# Motor_Lab_v8.net
KiCad netlist of a schematic drawn in EAGLE
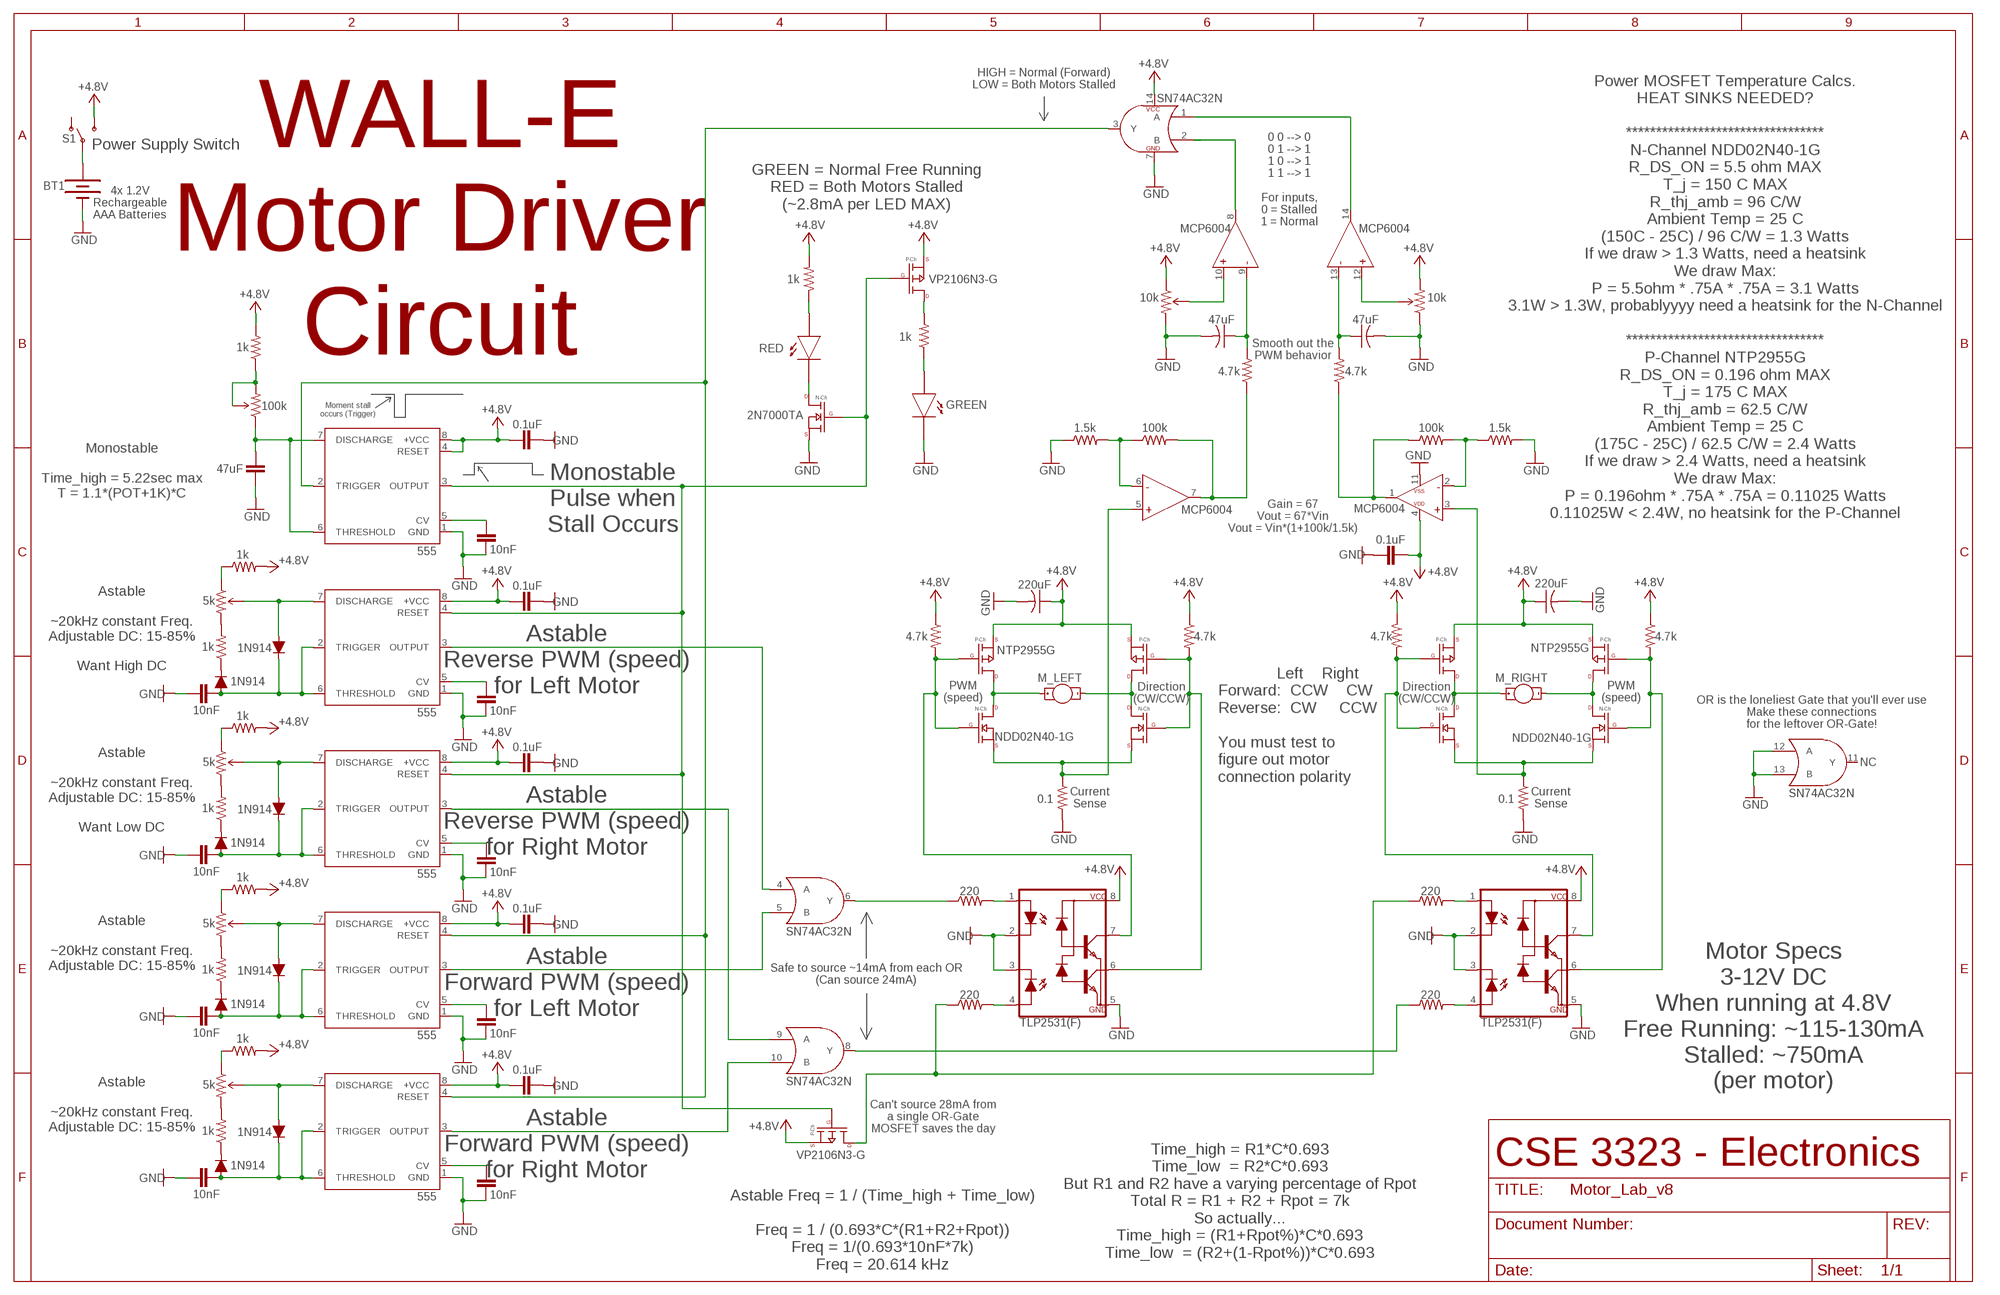
[diagram p0: schematic, sheet 1]

(export (version "E")
  (design (tool "Eeschema 10.0.6"))
  (components
    (comp (ref "BT1")
      (value "BATTERY-AAA")
      (footprint "eagle-import:BATTERY-AAA")
      (libsource (lib "eagle-import") (part "BATTERY-AAA"))
    )
    (comp (ref "C1")
      (value "220uF")
      (footprint "eagle-import:C025-024X044")
      (libsource (lib "eagle-import") (part "C-US025-024X044"))
    )
    (comp (ref "C2")
      (value "220uF")
      (footprint "eagle-import:C025-024X044")
      (libsource (lib "eagle-import") (part "C-US025-024X044"))
    )
    (comp (ref "C3")
      (value "0.1uF")
      (footprint "eagle-import:CAP-PTH-SMALL-KIT")
      (libsource (lib "eagle-import") (part "0.1UF-KIT-EZ-50V-20%"))
    )
    (comp (ref "C5")
      (value "0.1uF")
      (footprint "eagle-import:CAP-PTH-SMALL-KIT")
      (libsource (lib "eagle-import") (part "0.1UF-KIT-EZ-50V-20%"))
    )
    (comp (ref "C6")
      (value "10nF")
      (footprint "eagle-import:CAP-PTH-SMALL-KIT")
      (libsource (lib "eagle-import") (part "0.1UF-KIT-EZ-50V-20%"))
    )
    (comp (ref "C7")
      (value "10nF")
      (footprint "eagle-import:CAP-PTH-SMALL-KIT")
      (libsource (lib "eagle-import") (part "0.1UF-KIT-EZ-50V-20%"))
    )
    (comp (ref "C8")
      (value "0.1uF")
      (footprint "eagle-import:CAP-PTH-SMALL-KIT")
      (libsource (lib "eagle-import") (part "0.1UF-KIT-EZ-50V-20%"))
    )
    (comp (ref "C9")
      (value "10nF")
      (footprint "eagle-import:CAP-PTH-SMALL-KIT")
      (libsource (lib "eagle-import") (part "0.1UF-KIT-EZ-50V-20%"))
    )
    (comp (ref "C10")
      (value "0.1uF")
      (footprint "eagle-import:CAP-PTH-SMALL-KIT")
      (libsource (lib "eagle-import") (part "0.1UF-KIT-EZ-50V-20%"))
    )
    (comp (ref "C11")
      (value "10nF")
      (footprint "eagle-import:CAP-PTH-SMALL-KIT")
      (libsource (lib "eagle-import") (part "0.1UF-KIT-EZ-50V-20%"))
    )
    (comp (ref "C12")
      (value "0.1uF")
      (footprint "eagle-import:CAP-PTH-SMALL-KIT")
      (libsource (lib "eagle-import") (part "0.1UF-KIT-EZ-50V-20%"))
    )
    (comp (ref "C13")
      (value "10nF")
      (footprint "eagle-import:CAP-PTH-SMALL-KIT")
      (libsource (lib "eagle-import") (part "0.1UF-KIT-EZ-50V-20%"))
    )
    (comp (ref "C14")
      (value "0.1uF")
      (footprint "eagle-import:CAP-PTH-SMALL-KIT")
      (libsource (lib "eagle-import") (part "0.1UF-KIT-EZ-50V-20%"))
    )
    (comp (ref "C15")
      (value "10nF")
      (footprint "eagle-import:CAP-PTH-SMALL-KIT")
      (libsource (lib "eagle-import") (part "0.1UF-KIT-EZ-50V-20%"))
    )
    (comp (ref "C16")
      (value "10nF")
      (footprint "eagle-import:CAP-PTH-SMALL-KIT")
      (libsource (lib "eagle-import") (part "0.1UF-KIT-EZ-50V-20%"))
    )
    (comp (ref "C17")
      (value "10nF")
      (footprint "eagle-import:CAP-PTH-SMALL-KIT")
      (libsource (lib "eagle-import") (part "0.1UF-KIT-EZ-50V-20%"))
    )
    (comp (ref "C18")
      (value "10nF")
      (footprint "eagle-import:CAP-PTH-SMALL-KIT")
      (libsource (lib "eagle-import") (part "0.1UF-KIT-EZ-50V-20%"))
    )
    (comp (ref "C19")
      (value "47uF")
      (footprint "eagle-import:CAP-PTH-SMALL-KIT")
      (libsource (lib "eagle-import") (part "0.1UF-KIT-EZ-50V-20%"))
    )
    (comp (ref "C20")
      (value "47uF")
      (footprint "eagle-import:C025-024X044")
      (libsource (lib "eagle-import") (part "C-US025-024X044"))
    )
    (comp (ref "C22")
      (value "47uF")
      (footprint "eagle-import:C025-024X044")
      (libsource (lib "eagle-import") (part "C-US025-024X044"))
    )
    (comp (ref "D1")
      (value "RED")
      (footprint "eagle-import:LED5MM")
      (libsource (lib "eagle-import") (part "LED_5MM"))
    )
    (comp (ref "D2")
      (value "GREEN")
      (footprint "eagle-import:LED5MM")
      (libsource (lib "eagle-import") (part "LED_5MM"))
    )
    (comp (ref "D3")
      (value "1N914")
      (footprint "eagle-import:DIODE-1N4148")
      (libsource (lib "eagle-import") (part "DIODE-1N4148"))
    )
    (comp (ref "D4")
      (value "1N914")
      (footprint "eagle-import:DIODE-1N4148")
      (libsource (lib "eagle-import") (part "DIODE-1N4148"))
    )
    (comp (ref "D5")
      (value "1N914")
      (footprint "eagle-import:DIODE-1N4148")
      (libsource (lib "eagle-import") (part "DIODE-1N4148"))
    )
    (comp (ref "D6")
      (value "1N914")
      (footprint "eagle-import:DIODE-1N4148")
      (libsource (lib "eagle-import") (part "DIODE-1N4148"))
    )
    (comp (ref "D7")
      (value "1N914")
      (footprint "eagle-import:DIODE-1N4148")
      (libsource (lib "eagle-import") (part "DIODE-1N4148"))
    )
    (comp (ref "D8")
      (value "1N914")
      (footprint "eagle-import:DIODE-1N4148")
      (libsource (lib "eagle-import") (part "DIODE-1N4148"))
    )
    (comp (ref "D9")
      (value "1N914")
      (footprint "eagle-import:DIODE-1N4148")
      (libsource (lib "eagle-import") (part "DIODE-1N4148"))
    )
    (comp (ref "D10")
      (value "1N914")
      (footprint "eagle-import:DIODE-1N4148")
      (libsource (lib "eagle-import") (part "DIODE-1N4148"))
    )
    (comp (ref "IC1")
      (value "555")
      (footprint "eagle-import:DIP08")
      (libsource (lib "eagle-import") (part "555-TIMERP"))
    )
    (comp (ref "IC2")
      (value "555")
      (footprint "eagle-import:DIP08")
      (libsource (lib "eagle-import") (part "555-TIMERP"))
    )
    (comp (ref "IC3")
      (value "555")
      (footprint "eagle-import:DIP08")
      (libsource (lib "eagle-import") (part "555-TIMERP"))
    )
    (comp (ref "IC4")
      (value "555")
      (footprint "eagle-import:DIP08")
      (libsource (lib "eagle-import") (part "555-TIMERP"))
    )
    (comp (ref "IC5")
      (value "555")
      (footprint "eagle-import:DIP08")
      (libsource (lib "eagle-import") (part "555-TIMERP"))
    )
    (comp (ref "M_LEFT")
      (value "MOTOR10MM")
      (footprint "eagle-import:VIBE-MOTOR-10MM")
      (libsource (lib "eagle-import") (part "MOTOR10MM"))
    )
    (comp (ref "M_RIGHT")
      (value "MOTOR10MM")
      (footprint "eagle-import:VIBE-MOTOR-10MM")
      (libsource (lib "eagle-import") (part "MOTOR10MM"))
    )
    (comp (ref "POT1")
      (value "5k")
      (footprint "eagle-import:TRIM_POT_PTH")
      (libsource (lib "eagle-import") (part "TRIMPOT"))
    )
    (comp (ref "POT4")
      (value "5k")
      (footprint "eagle-import:TRIM_POT_PTH")
      (libsource (lib "eagle-import") (part "TRIMPOT"))
    )
    (comp (ref "POT5")
      (value "5k")
      (footprint "eagle-import:TRIM_POT_PTH")
      (libsource (lib "eagle-import") (part "TRIMPOT"))
    )
    (comp (ref "POT6")
      (value "5k")
      (footprint "eagle-import:TRIM_POT_PTH")
      (libsource (lib "eagle-import") (part "TRIMPOT"))
    )
    (comp (ref "POT7")
      (value "100k")
      (footprint "eagle-import:TRIM_POT_PTH")
      (libsource (lib "eagle-import") (part "TRIMPOT"))
    )
    (comp (ref "POT8")
      (value "10k")
      (footprint "eagle-import:TRIM_POT_PTH")
      (libsource (lib "eagle-import") (part "TRIMPOT"))
    )
    (comp (ref "POT9")
      (value "10k")
      (footprint "eagle-import:TRIM_POT_PTH")
      (libsource (lib "eagle-import") (part "TRIMPOT"))
    )
    (comp (ref "R1")
      (value "0.1")
      (footprint "eagle-import:0204V")
      (libsource (lib "eagle-import") (part "R-US_0204/2V"))
    )
    (comp (ref "R2")
      (value "0.1")
      (footprint "eagle-import:0204V")
      (libsource (lib "eagle-import") (part "R-US_0204/2V"))
    )
    (comp (ref "R3")
      (value "100k")
      (footprint "eagle-import:0204V")
      (libsource (lib "eagle-import") (part "R-US_0204/2V"))
    )
    (comp (ref "R4")
      (value "100k")
      (footprint "eagle-import:0204V")
      (libsource (lib "eagle-import") (part "R-US_0204/2V"))
    )
    (comp (ref "R5")
      (value "1.5k")
      (footprint "eagle-import:0204V")
      (libsource (lib "eagle-import") (part "R-US_0204/2V"))
    )
    (comp (ref "R6")
      (value "1.5k")
      (footprint "eagle-import:0204V")
      (libsource (lib "eagle-import") (part "R-US_0204/2V"))
    )
    (comp (ref "R7")
      (value "1k")
      (footprint "eagle-import:0204V")
      (libsource (lib "eagle-import") (part "R-US_0204/2V"))
    )
    (comp (ref "R8")
      (value "1k")
      (footprint "eagle-import:0204V")
      (libsource (lib "eagle-import") (part "R-US_0204/2V"))
    )
    (comp (ref "R9")
      (value "1k")
      (footprint "eagle-import:0204V")
      (libsource (lib "eagle-import") (part "R-US_0204/2V"))
    )
    (comp (ref "R10")
      (value "1k")
      (footprint "eagle-import:0204V")
      (libsource (lib "eagle-import") (part "R-US_0204/2V"))
    )
    (comp (ref "R11")
      (value "1k")
      (footprint "eagle-import:0204V")
      (libsource (lib "eagle-import") (part "R-US_0204/2V"))
    )
    (comp (ref "R12")
      (value "1k")
      (footprint "eagle-import:0204V")
      (libsource (lib "eagle-import") (part "R-US_0204/2V"))
    )
    (comp (ref "R13")
      (value "1k")
      (footprint "eagle-import:0204V")
      (libsource (lib "eagle-import") (part "R-US_0204/2V"))
    )
    (comp (ref "R14")
      (value "1k")
      (footprint "eagle-import:0204V")
      (libsource (lib "eagle-import") (part "R-US_0204/2V"))
    )
    (comp (ref "R15")
      (value "1k")
      (footprint "eagle-import:0204V")
      (libsource (lib "eagle-import") (part "R-US_0204/2V"))
    )
    (comp (ref "R16")
      (value "1k")
      (footprint "eagle-import:0204V")
      (libsource (lib "eagle-import") (part "R-US_0204/2V"))
    )
    (comp (ref "R19")
      (value "4.7k")
      (footprint "eagle-import:0204V")
      (libsource (lib "eagle-import") (part "R-US_0204/2V"))
    )
    (comp (ref "R20")
      (value "220")
      (footprint "eagle-import:0204V")
      (libsource (lib "eagle-import") (part "R-US_0204/2V"))
    )
    (comp (ref "R21")
      (value "4.7k")
      (footprint "eagle-import:0204V")
      (libsource (lib "eagle-import") (part "R-US_0204/2V"))
    )
    (comp (ref "R22")
      (value "4.7k")
      (footprint "eagle-import:0204V")
      (libsource (lib "eagle-import") (part "R-US_0204/2V"))
    )
    (comp (ref "R23")
      (value "4.7k")
      (footprint "eagle-import:0204V")
      (libsource (lib "eagle-import") (part "R-US_0204/2V"))
    )
    (comp (ref "R24")
      (value "4.7k")
      (footprint "eagle-import:0204V")
      (libsource (lib "eagle-import") (part "R-US_0204/2V"))
    )
    (comp (ref "R25")
      (value "4.7k")
      (footprint "eagle-import:0204V")
      (libsource (lib "eagle-import") (part "R-US_0204/2V"))
    )
    (comp (ref "R26")
      (value "220")
      (footprint "eagle-import:0204V")
      (libsource (lib "eagle-import") (part "R-US_0204/2V"))
    )
    (comp (ref "R27")
      (value "1k")
      (footprint "eagle-import:0204V")
      (libsource (lib "eagle-import") (part "R-US_0204/2V"))
    )
    (comp (ref "R28")
      (value "220")
      (footprint "eagle-import:0204V")
      (libsource (lib "eagle-import") (part "R-US_0204/2V"))
    )
    (comp (ref "R29")
      (value "220")
      (footprint "eagle-import:0204V")
      (libsource (lib "eagle-import") (part "R-US_0204/2V"))
    )
    (comp (ref "S1")
      (value "SWITCH-SPDT-PTH-11.6X4.0MM")
      (footprint "eagle-import:SWITCH_SPDT_PTH_11.6X4.0MM")
      (libsource (lib "eagle-import") (part "SWITCH-SPDT-PTH-11.6X4.0MM"))
    )
    (comp (ref "U$1")
      (value "STP3NK50Z")
      (footprint "eagle-import:TO92-")
      (libsource (lib "eagle-import") (part "MOSFET-N"))
    )
    (comp (ref "U$2")
      (value "NDD02N40-1G")
      (footprint "eagle-import:TO92-")
      (libsource (lib "eagle-import") (part "MOSFET-N"))
    )
    (comp (ref "U$3")
      (value "NDD02N40-1G")
      (footprint "eagle-import:TO92-")
      (libsource (lib "eagle-import") (part "MOSFET-N"))
    )
    (comp (ref "U$4")
      (value "STP3NK50Z")
      (footprint "eagle-import:TO92-")
      (libsource (lib "eagle-import") (part "MOSFET-N"))
    )
    (comp (ref "U$5")
      (value "NTP2955G")
      (footprint "eagle-import:TO92-")
      (libsource (lib "eagle-import") (part "MOSFET-P"))
    )
    (comp (ref "U$6")
      (value "NTP2955G")
      (footprint "eagle-import:TO92-")
      (libsource (lib "eagle-import") (part "MOSFET-P"))
    )
    (comp (ref "U$7")
      (value "NTP2955G")
      (footprint "eagle-import:TO92-")
      (libsource (lib "eagle-import") (part "MOSFET-P"))
    )
    (comp (ref "U$8")
      (value "NTP2955G")
      (footprint "eagle-import:TO92-")
      (libsource (lib "eagle-import") (part "MOSFET-P"))
    )
    (comp (ref "U$9")
      (value "2N7000TA")
      (footprint "eagle-import:TO92-")
      (libsource (lib "eagle-import") (part "MOSFET-N"))
    )
    (comp (ref "U$10")
      (value "VP2106N3-G")
      (footprint "eagle-import:TO92-")
      (libsource (lib "eagle-import") (part "MOSFET-P"))
    )
    (comp (ref "U$11")
      (value "SN74AC32N")
      (footprint "eagle-import:DIP14")
      (libsource (lib "eagle-import") (part "SN74AC32N"))
    )
    (comp (ref "U$12")
      (value "VP2106N3-G")
      (footprint "eagle-import:TO92-")
      (libsource (lib "eagle-import") (part "MOSFET-P"))
    )
    (comp (ref "U$13")
      (value "TLP2531(F)")
      (footprint "eagle-import:DIP08")
      (libsource (lib "eagle-import") (part "TLP2531(F)"))
    )
    (comp (ref "U$14")
      (value "TLP2531(F)")
      (footprint "eagle-import:DIP08")
      (libsource (lib "eagle-import") (part "TLP2531(F)"))
    )
    (comp (ref "U$15")
      (value "MCP6004")
      (footprint "eagle-import:DIP14")
      (libsource (lib "eagle-import") (part "MCP6004"))
    )
  )
  (nets
    (net (code "1") (name "+4.8V") (class "Default")
      (node (ref "C1") (pin "1") (pinfunction "1_1") (pintype "passive"))
      (node (ref "C10") (pin "1") (pinfunction "1_1") (pintype "passive"))
      (node (ref "C12") (pin "1") (pinfunction "1_1") (pintype "passive"))
      (node (ref "C14") (pin "1") (pinfunction "1_1") (pintype "passive"))
      (node (ref "C2") (pin "1") (pinfunction "1_1") (pintype "passive"))
      (node (ref "C3") (pin "2") (pinfunction "2_2") (pintype "passive"))
      (node (ref "C5") (pin "1") (pinfunction "1_1") (pintype "passive"))
      (node (ref "C8") (pin "1") (pinfunction "1_1") (pintype "passive"))
      (node (ref "IC1") (pin "8") (pinfunction "+VCC_8") (pintype "power_in"))
      (node (ref "IC2") (pin "8") (pinfunction "+VCC_8") (pintype "power_in"))
      (node (ref "IC3") (pin "8") (pinfunction "+VCC_8") (pintype "power_in"))
      (node (ref "IC4") (pin "8") (pinfunction "+VCC_8") (pintype "power_in"))
      (node (ref "IC5") (pin "4") (pinfunction "RESET_4") (pintype "input"))
      (node (ref "IC5") (pin "8") (pinfunction "+VCC_8") (pintype "power_in"))
      (node (ref "POT8") (pin "1") (pinfunction "CCW_1") (pintype "passive"))
      (node (ref "POT9") (pin "3") (pinfunction "CW_3") (pintype "passive"))
      (node (ref "R11") (pin "2") (pinfunction "2_2") (pintype "passive"))
      (node (ref "R13") (pin "2") (pinfunction "2_2") (pintype "passive"))
      (node (ref "R15") (pin "2") (pinfunction "2_2") (pintype "passive"))
      (node (ref "R19") (pin "1") (pinfunction "1_1") (pintype "passive"))
      (node (ref "R21") (pin "1") (pinfunction "1_1") (pintype "passive"))
      (node (ref "R23") (pin "1") (pinfunction "1_1") (pintype "passive"))
      (node (ref "R25") (pin "1") (pinfunction "1_1") (pintype "passive"))
      (node (ref "R27") (pin "2") (pinfunction "2_2") (pintype "passive"))
      (node (ref "R7") (pin "2") (pinfunction "2_2") (pintype "passive"))
      (node (ref "R9") (pin "2") (pinfunction "2_2") (pintype "passive"))
      (node (ref "S1") (pin "3") (pinfunction "S_3") (pintype "passive"))
      (node (ref "U$10") (pin "3") (pinfunction "SOURCE_3") (pintype "bidirectional"))
      (node (ref "U$11") (pin "14") (pinfunction "VCC_14") (pintype "bidirectional"))
      (node (ref "U$12") (pin "3") (pinfunction "SOURCE_3") (pintype "bidirectional"))
      (node (ref "U$13") (pin "8") (pinfunction "VCC_8") (pintype "passive"))
      (node (ref "U$14") (pin "8") (pinfunction "VCC_8") (pintype "passive"))
      (node (ref "U$15") (pin "4") (pinfunction "VDD_4") (pintype "power_in"))
      (node (ref "U$5") (pin "3") (pinfunction "SOURCE_3") (pintype "bidirectional"))
      (node (ref "U$6") (pin "3") (pinfunction "SOURCE_3") (pintype "bidirectional"))
      (node (ref "U$7") (pin "3") (pinfunction "SOURCE_3") (pintype "bidirectional"))
      (node (ref "U$8") (pin "3") (pinfunction "SOURCE_3") (pintype "bidirectional"))
    )
    (net (code "2") (name "GND") (class "Default")
      (node (ref "BT1") (pin "GND@1") (pinfunction "-_GND@1") (pintype "power_in"))
      (node (ref "C1") (pin "2") (pinfunction "2_2") (pintype "passive"))
      (node (ref "C10") (pin "2") (pinfunction "2_2") (pintype "passive"))
      (node (ref "C11") (pin "1") (pinfunction "1_1") (pintype "passive"))
      (node (ref "C12") (pin "2") (pinfunction "2_2") (pintype "passive"))
      (node (ref "C13") (pin "1") (pinfunction "1_1") (pintype "passive"))
      (node (ref "C14") (pin "2") (pinfunction "2_2") (pintype "passive"))
      (node (ref "C15") (pin "1") (pinfunction "1_1") (pintype "passive"))
      (node (ref "C16") (pin "1") (pinfunction "1_1") (pintype "passive"))
      (node (ref "C17") (pin "1") (pinfunction "1_1") (pintype "passive"))
      (node (ref "C18") (pin "1") (pinfunction "1_1") (pintype "passive"))
      (node (ref "C19") (pin "1") (pinfunction "1_1") (pintype "passive"))
      (node (ref "C2") (pin "2") (pinfunction "2_2") (pintype "passive"))
      (node (ref "C20") (pin "2") (pinfunction "2_2") (pintype "passive"))
      (node (ref "C22") (pin "2") (pinfunction "2_2") (pintype "passive"))
      (node (ref "C3") (pin "1") (pinfunction "1_1") (pintype "passive"))
      (node (ref "C5") (pin "2") (pinfunction "2_2") (pintype "passive"))
      (node (ref "C6") (pin "1") (pinfunction "1_1") (pintype "passive"))
      (node (ref "C7") (pin "1") (pinfunction "1_1") (pintype "passive"))
      (node (ref "C8") (pin "2") (pinfunction "2_2") (pintype "passive"))
      (node (ref "C9") (pin "1") (pinfunction "1_1") (pintype "passive"))
      (node (ref "D2") (pin "K") (pinfunction "P$2_K") (pintype "bidirectional"))
      (node (ref "IC1") (pin "1") (pinfunction "GND_1") (pintype "power_in"))
      (node (ref "IC2") (pin "1") (pinfunction "GND_1") (pintype "power_in"))
      (node (ref "IC3") (pin "1") (pinfunction "GND_1") (pintype "power_in"))
      (node (ref "IC4") (pin "1") (pinfunction "GND_1") (pintype "power_in"))
      (node (ref "IC5") (pin "1") (pinfunction "GND_1") (pintype "power_in"))
      (node (ref "POT8") (pin "3") (pinfunction "CW_3") (pintype "passive"))
      (node (ref "POT9") (pin "1") (pinfunction "CCW_1") (pintype "passive"))
      (node (ref "R1") (pin "2") (pinfunction "2_2") (pintype "passive"))
      (node (ref "R2") (pin "2") (pinfunction "2_2") (pintype "passive"))
      (node (ref "R5") (pin "1") (pinfunction "1_1") (pintype "passive"))
      (node (ref "R6") (pin "2") (pinfunction "2_2") (pintype "passive"))
      (node (ref "U$11") (pin "12") (pinfunction "A_12") (pintype "bidirectional"))
      (node (ref "U$11") (pin "13") (pinfunction "B_13") (pintype "bidirectional"))
      (node (ref "U$11") (pin "7") (pinfunction "GND_7") (pintype "bidirectional"))
      (node (ref "U$13") (pin "2") (pinfunction "C1_2") (pintype "passive"))
      (node (ref "U$13") (pin "3") (pinfunction "C2_3") (pintype "passive"))
      (node (ref "U$13") (pin "5") (pinfunction "GND_5") (pintype "power_in"))
      (node (ref "U$14") (pin "2") (pinfunction "C1_2") (pintype "passive"))
      (node (ref "U$14") (pin "3") (pinfunction "C2_3") (pintype "passive"))
      (node (ref "U$14") (pin "5") (pinfunction "GND_5") (pintype "power_in"))
      (node (ref "U$15") (pin "11") (pinfunction "VSS_11") (pintype "power_in"))
      (node (ref "U$9") (pin "1") (pinfunction "SOURCE_1") (pintype "bidirectional"))
    )
    (net (code "3") (name "Net-(BT1-+)") (class "Default")
      (node (ref "BT1") (pin "PWR@1") (pinfunction "+_PWR@1") (pintype "power_in"))
      (node (ref "S1") (pin "2") (pinfunction "P_2") (pintype "passive"))
    )
    (net (code "4") (name "Net-(D1-P$1)") (class "Default")
      (node (ref "D1") (pin "A") (pinfunction "P$1_A") (pintype "bidirectional"))
      (node (ref "R7") (pin "1") (pinfunction "1_1") (pintype "passive"))
    )
    (net (code "5") (name "Net-(D1-P$2)") (class "Default")
      (node (ref "D1") (pin "K") (pinfunction "P$2_K") (pintype "bidirectional"))
      (node (ref "U$9") (pin "3") (pinfunction "DRAIN_3") (pintype "bidirectional"))
    )
    (net (code "6") (name "Net-(D2-P$1)") (class "Default")
      (node (ref "D2") (pin "A") (pinfunction "P$1_A") (pintype "bidirectional"))
      (node (ref "R8") (pin "1") (pinfunction "1_1") (pintype "passive"))
    )
    (net (code "7") (name "Net-(D3-PadC)") (class "Default")
      (node (ref "D3") (pin "C") (pinfunction "C_C") (pintype "passive"))
      (node (ref "R10") (pin "1") (pinfunction "1_1") (pintype "passive"))
    )
    (net (code "8") (name "Net-(D5-PadC)") (class "Default")
      (node (ref "D5") (pin "C") (pinfunction "C_C") (pintype "passive"))
      (node (ref "R12") (pin "1") (pinfunction "1_1") (pintype "passive"))
    )
    (net (code "9") (name "Net-(D7-PadC)") (class "Default")
      (node (ref "D7") (pin "C") (pinfunction "C_C") (pintype "passive"))
      (node (ref "R14") (pin "1") (pinfunction "1_1") (pintype "passive"))
    )
    (net (code "10") (name "Net-(D9-PadC)") (class "Default")
      (node (ref "D9") (pin "C") (pinfunction "C_C") (pintype "passive"))
      (node (ref "R16") (pin "1") (pinfunction "1_1") (pintype "passive"))
    )
    (net (code "11") (name "Net-(IC1-CV)") (class "Default")
      (node (ref "C6") (pin "2") (pinfunction "2_2") (pintype "passive"))
      (node (ref "IC1") (pin "5") (pinfunction "CV_5") (pintype "input"))
    )
    (net (code "12") (name "Net-(IC1-DISCHARGE)") (class "Default")
      (node (ref "D4") (pin "A") (pinfunction "A_A") (pintype "passive"))
      (node (ref "IC1") (pin "7") (pinfunction "DISCHARGE_7") (pintype "input"))
      (node (ref "POT1") (pin "2") (pinfunction "WIPER_2") (pintype "passive"))
    )
    (net (code "13") (name "Net-(IC1-OUTPUT)") (class "Default")
      (node (ref "IC1") (pin "3") (pinfunction "OUTPUT_3") (pintype "output"))
      (node (ref "U$11") (pin "10") (pinfunction "B_10") (pintype "bidirectional"))
    )
    (net (code "14") (name "Net-(IC1-RESET)") (class "Default")
      (node (ref "IC1") (pin "4") (pinfunction "RESET_4") (pintype "input"))
      (node (ref "IC2") (pin "4") (pinfunction "RESET_4") (pintype "input"))
      (node (ref "IC5") (pin "2") (pinfunction "TRIGGER_2") (pintype "input"))
      (node (ref "U$11") (pin "3") (pinfunction "Y_3") (pintype "bidirectional"))
    )
    (net (code "15") (name "Net-(IC1-THRESHOLD)") (class "Default")
      (node (ref "C15") (pin "2") (pinfunction "2_2") (pintype "passive"))
      (node (ref "D3") (pin "A") (pinfunction "A_A") (pintype "passive"))
      (node (ref "D4") (pin "C") (pinfunction "C_C") (pintype "passive"))
      (node (ref "IC1") (pin "2") (pinfunction "TRIGGER_2") (pintype "input"))
      (node (ref "IC1") (pin "6") (pinfunction "THRESHOLD_6") (pintype "input"))
    )
    (net (code "16") (name "Net-(IC2-CV)") (class "Default")
      (node (ref "C7") (pin "2") (pinfunction "2_2") (pintype "passive"))
      (node (ref "IC2") (pin "5") (pinfunction "CV_5") (pintype "input"))
    )
    (net (code "17") (name "Net-(IC2-DISCHARGE)") (class "Default")
      (node (ref "D6") (pin "A") (pinfunction "A_A") (pintype "passive"))
      (node (ref "IC2") (pin "7") (pinfunction "DISCHARGE_7") (pintype "input"))
      (node (ref "POT4") (pin "2") (pinfunction "WIPER_2") (pintype "passive"))
    )
    (net (code "18") (name "Net-(IC2-OUTPUT)") (class "Default")
      (node (ref "IC2") (pin "3") (pinfunction "OUTPUT_3") (pintype "output"))
      (node (ref "U$11") (pin "5") (pinfunction "B_5") (pintype "bidirectional"))
    )
    (net (code "19") (name "Net-(IC2-THRESHOLD)") (class "Default")
      (node (ref "C16") (pin "2") (pinfunction "2_2") (pintype "passive"))
      (node (ref "D5") (pin "A") (pinfunction "A_A") (pintype "passive"))
      (node (ref "D6") (pin "C") (pinfunction "C_C") (pintype "passive"))
      (node (ref "IC2") (pin "2") (pinfunction "TRIGGER_2") (pintype "input"))
      (node (ref "IC2") (pin "6") (pinfunction "THRESHOLD_6") (pintype "input"))
    )
    (net (code "20") (name "Net-(IC3-CV)") (class "Default")
      (node (ref "C9") (pin "2") (pinfunction "2_2") (pintype "passive"))
      (node (ref "IC3") (pin "5") (pinfunction "CV_5") (pintype "input"))
    )
    (net (code "21") (name "Net-(IC3-DISCHARGE)") (class "Default")
      (node (ref "D8") (pin "A") (pinfunction "A_A") (pintype "passive"))
      (node (ref "IC3") (pin "7") (pinfunction "DISCHARGE_7") (pintype "input"))
      (node (ref "POT5") (pin "2") (pinfunction "WIPER_2") (pintype "passive"))
    )
    (net (code "22") (name "Net-(IC3-OUTPUT)") (class "Default")
      (node (ref "IC3") (pin "3") (pinfunction "OUTPUT_3") (pintype "output"))
      (node (ref "U$11") (pin "9") (pinfunction "A_9") (pintype "bidirectional"))
    )
    (net (code "23") (name "Net-(IC3-RESET)") (class "Default")
      (node (ref "IC3") (pin "4") (pinfunction "RESET_4") (pintype "input"))
      (node (ref "IC4") (pin "4") (pinfunction "RESET_4") (pintype "input"))
      (node (ref "IC5") (pin "3") (pinfunction "OUTPUT_3") (pintype "output"))
      (node (ref "U$10") (pin "2") (pinfunction "GATE_2") (pintype "bidirectional"))
      (node (ref "U$12") (pin "2") (pinfunction "GATE_2") (pintype "bidirectional"))
      (node (ref "U$9") (pin "2") (pinfunction "GATE_2") (pintype "bidirectional"))
    )
    (net (code "24") (name "Net-(IC3-THRESHOLD)") (class "Default")
      (node (ref "C17") (pin "2") (pinfunction "2_2") (pintype "passive"))
      (node (ref "D7") (pin "A") (pinfunction "A_A") (pintype "passive"))
      (node (ref "D8") (pin "C") (pinfunction "C_C") (pintype "passive"))
      (node (ref "IC3") (pin "2") (pinfunction "TRIGGER_2") (pintype "input"))
      (node (ref "IC3") (pin "6") (pinfunction "THRESHOLD_6") (pintype "input"))
    )
    (net (code "25") (name "Net-(IC4-CV)") (class "Default")
      (node (ref "C11") (pin "2") (pinfunction "2_2") (pintype "passive"))
      (node (ref "IC4") (pin "5") (pinfunction "CV_5") (pintype "input"))
    )
    (net (code "26") (name "Net-(IC4-DISCHARGE)") (class "Default")
      (node (ref "D10") (pin "A") (pinfunction "A_A") (pintype "passive"))
      (node (ref "IC4") (pin "7") (pinfunction "DISCHARGE_7") (pintype "input"))
      (node (ref "POT6") (pin "2") (pinfunction "WIPER_2") (pintype "passive"))
    )
    (net (code "27") (name "Net-(IC4-OUTPUT)") (class "Default")
      (node (ref "IC4") (pin "3") (pinfunction "OUTPUT_3") (pintype "output"))
      (node (ref "U$11") (pin "4") (pinfunction "A_4") (pintype "bidirectional"))
    )
    (net (code "28") (name "Net-(IC4-THRESHOLD)") (class "Default")
      (node (ref "C18") (pin "2") (pinfunction "2_2") (pintype "passive"))
      (node (ref "D10") (pin "C") (pinfunction "C_C") (pintype "passive"))
      (node (ref "D9") (pin "A") (pinfunction "A_A") (pintype "passive"))
      (node (ref "IC4") (pin "2") (pinfunction "TRIGGER_2") (pintype "input"))
      (node (ref "IC4") (pin "6") (pinfunction "THRESHOLD_6") (pintype "input"))
    )
    (net (code "29") (name "Net-(IC5-CV)") (class "Default")
      (node (ref "C13") (pin "2") (pinfunction "2_2") (pintype "passive"))
      (node (ref "IC5") (pin "5") (pinfunction "CV_5") (pintype "input"))
    )
    (net (code "30") (name "Net-(IC5-DISCHARGE)") (class "Default")
      (node (ref "C19") (pin "2") (pinfunction "2_2") (pintype "passive"))
      (node (ref "IC5") (pin "6") (pinfunction "THRESHOLD_6") (pintype "input"))
      (node (ref "IC5") (pin "7") (pinfunction "DISCHARGE_7") (pintype "input"))
      (node (ref "POT7") (pin "1") (pinfunction "CCW_1") (pintype "passive"))
    )
    (net (code "31") (name "Net-(POT1-CCW)") (class "Default")
      (node (ref "POT1") (pin "1") (pinfunction "CCW_1") (pintype "passive"))
      (node (ref "R9") (pin "1") (pinfunction "1_1") (pintype "passive"))
    )
    (net (code "32") (name "Net-(POT1-CW)") (class "Default")
      (node (ref "POT1") (pin "3") (pinfunction "CW_3") (pintype "passive"))
      (node (ref "R10") (pin "2") (pinfunction "2_2") (pintype "passive"))
    )
    (net (code "33") (name "Net-(POT4-CCW)") (class "Default")
      (node (ref "POT4") (pin "1") (pinfunction "CCW_1") (pintype "passive"))
      (node (ref "R11") (pin "1") (pinfunction "1_1") (pintype "passive"))
    )
    (net (code "34") (name "Net-(POT4-CW)") (class "Default")
      (node (ref "POT4") (pin "3") (pinfunction "CW_3") (pintype "passive"))
      (node (ref "R12") (pin "2") (pinfunction "2_2") (pintype "passive"))
    )
    (net (code "35") (name "Net-(POT5-CCW)") (class "Default")
      (node (ref "POT5") (pin "1") (pinfunction "CCW_1") (pintype "passive"))
      (node (ref "R13") (pin "1") (pinfunction "1_1") (pintype "passive"))
    )
    (net (code "36") (name "Net-(POT5-CW)") (class "Default")
      (node (ref "POT5") (pin "3") (pinfunction "CW_3") (pintype "passive"))
      (node (ref "R14") (pin "2") (pinfunction "2_2") (pintype "passive"))
    )
    (net (code "37") (name "Net-(POT6-CCW)") (class "Default")
      (node (ref "POT6") (pin "1") (pinfunction "CCW_1") (pintype "passive"))
      (node (ref "R15") (pin "1") (pinfunction "1_1") (pintype "passive"))
    )
    (net (code "38") (name "Net-(POT6-CW)") (class "Default")
      (node (ref "POT6") (pin "3") (pinfunction "CW_3") (pintype "passive"))
      (node (ref "R16") (pin "2") (pinfunction "2_2") (pintype "passive"))
    )
    (net (code "39") (name "Net-(POT7-CW)") (class "Default")
      (node (ref "POT7") (pin "2") (pinfunction "WIPER_2") (pintype "passive"))
      (node (ref "POT7") (pin "3") (pinfunction "CW_3") (pintype "passive"))
      (node (ref "R27") (pin "1") (pinfunction "1_1") (pintype "passive"))
    )
    (net (code "40") (name "Net-(POT8-WIPER)") (class "Default")
      (node (ref "POT8") (pin "2") (pinfunction "WIPER_2") (pintype "passive"))
      (node (ref "U$15") (pin "10") (pinfunction "IN+_10") (pintype "bidirectional"))
    )
    (net (code "41") (name "Net-(POT9-WIPER)") (class "Default")
      (node (ref "POT9") (pin "2") (pinfunction "WIPER_2") (pintype "passive"))
      (node (ref "U$15") (pin "12") (pinfunction "IN+_12") (pintype "bidirectional"))
    )
    (net (code "42") (name "Net-(U$1-DRAIN)") (class "Default")
      (node (ref "M_LEFT") (pin "+") (pinfunction "+_+") (pintype "bidirectional"))
      (node (ref "U$1") (pin "3") (pinfunction "DRAIN_3") (pintype "bidirectional"))
      (node (ref "U$5") (pin "1") (pinfunction "DRAIN_1") (pintype "bidirectional"))
    )
    (net (code "43") (name "Net-(U$1-GATE)") (class "Default")
      (node (ref "R19") (pin "2") (pinfunction "2_2") (pintype "passive"))
      (node (ref "U$1") (pin "2") (pinfunction "GATE_2") (pintype "bidirectional"))
      (node (ref "U$13") (pin "7") (pinfunction "VO1_7") (pintype "passive"))
      (node (ref "U$5") (pin "2") (pinfunction "GATE_2") (pintype "bidirectional"))
    )
    (net (code "44") (name "Net-(U$1-SOURCE)") (class "Default")
      (node (ref "R1") (pin "1") (pinfunction "1_1") (pintype "passive"))
      (node (ref "U$1") (pin "1") (pinfunction "SOURCE_1") (pintype "bidirectional"))
      (node (ref "U$15") (pin "5") (pinfunction "IN+_5") (pintype "bidirectional"))
      (node (ref "U$2") (pin "1") (pinfunction "SOURCE_1") (pintype "bidirectional"))
    )
    (net (code "45") (name "Net-(U$2-DRAIN)") (class "Default")
      (node (ref "M_LEFT") (pin "-") (pinfunction "-_-") (pintype "bidirectional"))
      (node (ref "U$2") (pin "3") (pinfunction "DRAIN_3") (pintype "bidirectional"))
      (node (ref "U$6") (pin "1") (pinfunction "DRAIN_1") (pintype "bidirectional"))
    )
    (net (code "46") (name "Net-(U$3-DRAIN)") (class "Default")
      (node (ref "M_RIGHT") (pin "+") (pinfunction "+_+") (pintype "bidirectional"))
      (node (ref "U$3") (pin "3") (pinfunction "DRAIN_3") (pintype "bidirectional"))
      (node (ref "U$7") (pin "1") (pinfunction "DRAIN_1") (pintype "bidirectional"))
    )
    (net (code "47") (name "Net-(U$4-DRAIN)") (class "Default")
      (node (ref "M_RIGHT") (pin "-") (pinfunction "-_-") (pintype "bidirectional"))
      (node (ref "U$4") (pin "3") (pinfunction "DRAIN_3") (pintype "bidirectional"))
      (node (ref "U$8") (pin "1") (pinfunction "DRAIN_1") (pintype "bidirectional"))
    )
    (net (code "48") (name "Net-(U$10-DRAIN)") (class "Default")
      (node (ref "R8") (pin "2") (pinfunction "2_2") (pintype "passive"))
      (node (ref "U$10") (pin "1") (pinfunction "DRAIN_1") (pintype "bidirectional"))
    )
    (net (code "49") (name "Net-(U$11A-A)") (class "Default")
      (node (ref "U$11") (pin "1") (pinfunction "A_1") (pintype "bidirectional"))
      (node (ref "U$15") (pin "14") (pinfunction "OUT_14") (pintype "bidirectional"))
    )
    (net (code "50") (name "Net-(U$11A-B)") (class "Default")
      (node (ref "U$11") (pin "2") (pinfunction "B_2") (pintype "bidirectional"))
      (node (ref "U$15") (pin "8") (pinfunction "OUT_8") (pintype "bidirectional"))
    )
    (net (code "51") (name "Net-(U$11B-Y)") (class "Default")
      (node (ref "R20") (pin "1") (pinfunction "1_1") (pintype "passive"))
      (node (ref "U$11") (pin "6") (pinfunction "Y_6") (pintype "bidirectional"))
    )
    (net (code "52") (name "Net-(U$11C-Y)") (class "Default")
      (node (ref "R29") (pin "1") (pinfunction "1_1") (pintype "passive"))
      (node (ref "U$11") (pin "8") (pinfunction "Y_8") (pintype "bidirectional"))
    )
    (net (code "53") (name "Net-(U$12-DRAIN)") (class "Default")
      (node (ref "R26") (pin "1") (pinfunction "1_1") (pintype "passive"))
      (node (ref "R28") (pin "1") (pinfunction "1_1") (pintype "passive"))
      (node (ref "U$12") (pin "1") (pinfunction "DRAIN_1") (pintype "bidirectional"))
    )
    (net (code "54") (name "Net-(U$13-A1)") (class "Default")
      (node (ref "R20") (pin "2") (pinfunction "2_2") (pintype "passive"))
      (node (ref "U$13") (pin "1") (pinfunction "A1_1") (pintype "passive"))
    )
    (net (code "55") (name "Net-(U$13-A2)") (class "Default")
      (node (ref "R28") (pin "2") (pinfunction "2_2") (pintype "passive"))
      (node (ref "U$13") (pin "4") (pinfunction "A2_4") (pintype "passive"))
    )
    (net (code "56") (name "Net-(U$13-VO2)") (class "Default")
      (node (ref "R25") (pin "2") (pinfunction "2_2") (pintype "passive"))
      (node (ref "U$13") (pin "6") (pinfunction "VO2_6") (pintype "passive"))
      (node (ref "U$2") (pin "2") (pinfunction "GATE_2") (pintype "bidirectional"))
      (node (ref "U$6") (pin "2") (pinfunction "GATE_2") (pintype "bidirectional"))
    )
    (net (code "57") (name "Net-(U$14-A1)") (class "Default")
      (node (ref "R26") (pin "2") (pinfunction "2_2") (pintype "passive"))
      (node (ref "U$14") (pin "1") (pinfunction "A1_1") (pintype "passive"))
    )
    (net (code "58") (name "Net-(U$14-A2)") (class "Default")
      (node (ref "R29") (pin "2") (pinfunction "2_2") (pintype "passive"))
      (node (ref "U$14") (pin "4") (pinfunction "A2_4") (pintype "passive"))
    )
    (net (code "59") (name "Net-(U$14-VO1)") (class "Default")
      (node (ref "R21") (pin "2") (pinfunction "2_2") (pintype "passive"))
      (node (ref "U$14") (pin "7") (pinfunction "VO1_7") (pintype "passive"))
      (node (ref "U$3") (pin "2") (pinfunction "GATE_2") (pintype "bidirectional"))
      (node (ref "U$7") (pin "2") (pinfunction "GATE_2") (pintype "bidirectional"))
    )
    (net (code "60") (name "Net-(U$14-VO2)") (class "Default")
      (node (ref "R23") (pin "2") (pinfunction "2_2") (pintype "passive"))
      (node (ref "U$14") (pin "6") (pinfunction "VO2_6") (pintype "passive"))
      (node (ref "U$4") (pin "2") (pinfunction "GATE_2") (pintype "bidirectional"))
      (node (ref "U$8") (pin "2") (pinfunction "GATE_2") (pintype "bidirectional"))
    )
    (net (code "61") (name "Net-(U$15A-IN+)") (class "Default")
      (node (ref "R2") (pin "1") (pinfunction "1_1") (pintype "passive"))
      (node (ref "U$15") (pin "3") (pinfunction "IN+_3") (pintype "bidirectional"))
      (node (ref "U$3") (pin "1") (pinfunction "SOURCE_1") (pintype "bidirectional"))
      (node (ref "U$4") (pin "1") (pinfunction "SOURCE_1") (pintype "bidirectional"))
    )
    (net (code "62") (name "Net-(U$15A-IN-)") (class "Default")
      (node (ref "R4") (pin "2") (pinfunction "2_2") (pintype "passive"))
      (node (ref "R6") (pin "1") (pinfunction "1_1") (pintype "passive"))
      (node (ref "U$15") (pin "2") (pinfunction "IN-_2") (pintype "bidirectional"))
    )
    (net (code "63") (name "Net-(U$15A-OUT)") (class "Default")
      (node (ref "R24") (pin "1") (pinfunction "1_1") (pintype "passive"))
      (node (ref "R4") (pin "1") (pinfunction "1_1") (pintype "passive"))
      (node (ref "U$15") (pin "1") (pinfunction "OUT_1") (pintype "bidirectional"))
    )
    (net (code "64") (name "Net-(U$15B-IN-)") (class "Default")
      (node (ref "R3") (pin "1") (pinfunction "1_1") (pintype "passive"))
      (node (ref "R5") (pin "2") (pinfunction "2_2") (pintype "passive"))
      (node (ref "U$15") (pin "6") (pinfunction "IN-_6") (pintype "bidirectional"))
    )
    (net (code "65") (name "Net-(U$15B-OUT)") (class "Default")
      (node (ref "R22") (pin "1") (pinfunction "1_1") (pintype "passive"))
      (node (ref "R3") (pin "2") (pinfunction "2_2") (pintype "passive"))
      (node (ref "U$15") (pin "7") (pinfunction "OUT_7") (pintype "bidirectional"))
    )
    (net (code "66") (name "Net-(U$15C-IN-)") (class "Default")
      (node (ref "C22") (pin "1") (pinfunction "1_1") (pintype "passive"))
      (node (ref "R22") (pin "2") (pinfunction "2_2") (pintype "passive"))
      (node (ref "U$15") (pin "9") (pinfunction "IN-_9") (pintype "bidirectional"))
    )
    (net (code "67") (name "Net-(U$15D-IN-)") (class "Default")
      (node (ref "C20") (pin "1") (pinfunction "1_1") (pintype "passive"))
      (node (ref "R24") (pin "2") (pinfunction "2_2") (pintype "passive"))
      (node (ref "U$15") (pin "13") (pinfunction "IN-_13") (pintype "bidirectional"))
    )
    (net (code "68") (name "unconnected-(S1-O-Pad1)") (class "Default")
      (node (ref "S1") (pin "1") (pinfunction "O_1") (pintype "passive"))
    )
    (net (code "69") (name "unconnected-(U$11D-Y-Pad11)") (class "Default")
      (node (ref "U$11") (pin "11") (pinfunction "Y_11") (pintype "bidirectional"))
    )
  )
)
